# core.net
KiCad netlist of a schematic drawn in Altium Designer
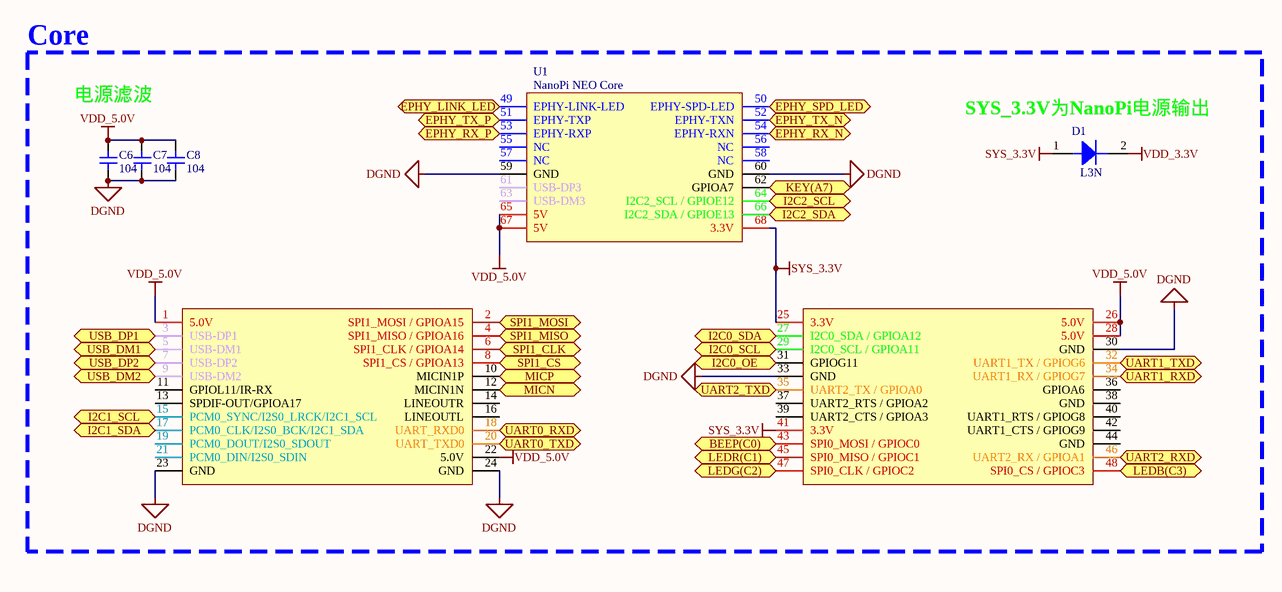
[diagram p0: core.SchDoc]

(export (version "E")
  (design (tool "Eeschema 10.0.6"))
  (components
    (comp (ref "C6")
      (value "104")
      (footprint "0805C")
      (description "无极贴片电容")
      (libsource (lib "集大电协1.5") (part "Cap1"))
    )
    (comp (ref "C7")
      (value "104")
      (footprint "0805C")
      (description "无极贴片电容")
      (libsource (lib "集大电协1.5") (part "Cap1"))
    )
    (comp (ref "C8")
      (value "104")
      (footprint "0805C")
      (description "无极贴片电容")
      (libsource (lib "集大电协1.5") (part "Cap1"))
    )
    (comp (ref "D1")
      (value "L3N")
      (footprint "SOD-123")
      (description "二极管30V/2A")
      (libsource (lib "集大电协1.5") (part "Diode"))
    )
    (comp (ref "U1")
      (value "NanoPi NEO Core")
      (footprint "NanoPi NEO Core(无引脚名)")
      (libsource (lib "集大电协1.5") (part "NanoPi NEO Core"))
    )
  )
  (nets
    (net (code "1") (name "/BEEP(C0)") (class "Default")
      (node (ref "U1") (pin "43") (pinfunction "SPI0_MOSI_/_GPIOC0_43") (pintype "passive"))
    )
    (net (code "2") (name "/EPHY_LINK_LED") (class "Default")
      (node (ref "U1") (pin "49") (pinfunction "EPHY-LINK-LED_49") (pintype "passive"))
    )
    (net (code "3") (name "/EPHY_RX_N") (class "Default")
      (node (ref "U1") (pin "54") (pinfunction "EPHY-RXN_54") (pintype "passive"))
    )
    (net (code "4") (name "/EPHY_RX_P") (class "Default")
      (node (ref "U1") (pin "53") (pinfunction "EPHY-RXP_53") (pintype "passive"))
    )
    (net (code "5") (name "/EPHY_SPD_LED") (class "Default")
      (node (ref "U1") (pin "50") (pinfunction "EPHY-SPD-LED_50") (pintype "passive"))
    )
    (net (code "6") (name "/EPHY_TX_N") (class "Default")
      (node (ref "U1") (pin "52") (pinfunction "EPHY-TXN_52") (pintype "passive"))
    )
    (net (code "7") (name "/EPHY_TX_P") (class "Default")
      (node (ref "U1") (pin "51") (pinfunction "EPHY-TXP_51") (pintype "passive"))
    )
    (net (code "8") (name "/I2C0_OE") (class "Default")
      (node (ref "U1") (pin "31") (pinfunction "GPIOG11_31") (pintype "passive"))
    )
    (net (code "9") (name "/I2C0_SCL") (class "Default")
      (node (ref "U1") (pin "29") (pinfunction "I2C0_SCL_/_GPIOA11_29") (pintype "passive"))
    )
    (net (code "10") (name "/I2C0_SDA") (class "Default")
      (node (ref "U1") (pin "27") (pinfunction "I2C0_SDA_/_GPIOA12_27") (pintype "passive"))
    )
    (net (code "11") (name "/I2C1_SCL") (class "Default")
      (node (ref "U1") (pin "15") (pinfunction "PCM0_SYNC/I2S0_LRCK/I2C1_SCL_15") (pintype "passive"))
    )
    (net (code "12") (name "/I2C1_SDA") (class "Default")
      (node (ref "U1") (pin "17") (pinfunction "PCM0_CLK/I2S0_BCK/I2C1_SDA_17") (pintype "passive"))
    )
    (net (code "13") (name "/I2C2_SCL") (class "Default")
      (node (ref "U1") (pin "64") (pinfunction "I2C2_SCL_/_GPIOE12_64") (pintype "passive"))
    )
    (net (code "14") (name "/I2C2_SDA") (class "Default")
      (node (ref "U1") (pin "66") (pinfunction "I2C2_SDA_/_GPIOE13_66") (pintype "passive"))
    )
    (net (code "15") (name "/KEY(A7)") (class "Default")
      (node (ref "U1") (pin "62") (pinfunction "GPIOA7_62") (pintype "passive"))
    )
    (net (code "16") (name "/LEDB(C3)") (class "Default")
      (node (ref "U1") (pin "48") (pinfunction "SPI0_CS_/_GPIOC3_48") (pintype "passive"))
    )
    (net (code "17") (name "/LEDG(C2)") (class "Default")
      (node (ref "U1") (pin "47") (pinfunction "SPI0_CLK_/_GPIOC2_47") (pintype "passive"))
    )
    (net (code "18") (name "/LEDR(C1)") (class "Default")
      (node (ref "U1") (pin "45") (pinfunction "SPI0_MISO_/_GPIOC1_45") (pintype "passive"))
    )
    (net (code "19") (name "/MICN") (class "Default")
      (node (ref "U1") (pin "12") (pinfunction "MICIN1N_12") (pintype "passive"))
    )
    (net (code "20") (name "/MICP") (class "Default")
      (node (ref "U1") (pin "10") (pinfunction "MICIN1P_10") (pintype "passive"))
    )
    (net (code "21") (name "/SPI1_CLK") (class "Default")
      (node (ref "U1") (pin "6") (pinfunction "SPI1_CLK_/_GPIOA14_6") (pintype "passive"))
    )
    (net (code "22") (name "/SPI1_CS") (class "Default")
      (node (ref "U1") (pin "8") (pinfunction "SPI1_CS_/_GPIOA13_8") (pintype "passive"))
    )
    (net (code "23") (name "/SPI1_MISO") (class "Default")
      (node (ref "U1") (pin "4") (pinfunction "SPI1_MISO_/_GPIOA16_4") (pintype "passive"))
    )
    (net (code "24") (name "/SPI1_MOSI") (class "Default")
      (node (ref "U1") (pin "2") (pinfunction "SPI1_MOSI_/_GPIOA15_2") (pintype "passive"))
    )
    (net (code "25") (name "/UART0_RXD") (class "Default")
      (node (ref "U1") (pin "18") (pinfunction "UART_RXD0_18") (pintype "passive"))
    )
    (net (code "26") (name "/UART0_TXD") (class "Default")
      (node (ref "U1") (pin "20") (pinfunction "UART_TXD0_20") (pintype "passive"))
    )
    (net (code "27") (name "/UART1_RXD") (class "Default")
      (node (ref "U1") (pin "34") (pinfunction "UART1_RX_/_GPIOG7_34") (pintype "passive"))
    )
    (net (code "28") (name "/UART1_TXD") (class "Default")
      (node (ref "U1") (pin "32") (pinfunction "UART1_TX_/_GPIOG6_32") (pintype "passive"))
    )
    (net (code "29") (name "/UART2_RXD") (class "Default")
      (node (ref "U1") (pin "46") (pinfunction "UART2_RX_/_GPIOA1_46") (pintype "passive"))
    )
    (net (code "30") (name "/UART2_TXD") (class "Default")
      (node (ref "U1") (pin "35") (pinfunction "UART2_TX_/_GPIOA0_35") (pintype "passive"))
    )
    (net (code "31") (name "/USB_DM1") (class "Default")
      (node (ref "U1") (pin "5") (pinfunction "USB-DM1_5") (pintype "passive"))
    )
    (net (code "32") (name "/USB_DM2") (class "Default")
      (node (ref "U1") (pin "9") (pinfunction "USB-DM2_9") (pintype "passive"))
    )
    (net (code "33") (name "/USB_DP1") (class "Default")
      (node (ref "U1") (pin "3") (pinfunction "USB-DP1_3") (pintype "passive"))
    )
    (net (code "34") (name "/USB_DP2") (class "Default")
      (node (ref "U1") (pin "7") (pinfunction "USB-DP2_7") (pintype "passive"))
    )
    (net (code "35") (name "DGND") (class "Default")
      (node (ref "C6") (pin "1") (pinfunction "1_1") (pintype "passive"))
      (node (ref "C7") (pin "1") (pinfunction "1_1") (pintype "passive"))
      (node (ref "C8") (pin "1") (pinfunction "1_1") (pintype "passive"))
      (node (ref "U1") (pin "23") (pinfunction "GND_23") (pintype "passive"))
      (node (ref "U1") (pin "24") (pinfunction "GND_24") (pintype "passive"))
      (node (ref "U1") (pin "30") (pinfunction "GND_30") (pintype "passive"))
      (node (ref "U1") (pin "33") (pinfunction "GND_33") (pintype "passive"))
      (node (ref "U1") (pin "59") (pinfunction "GND_59") (pintype "passive"))
      (node (ref "U1") (pin "60") (pinfunction "GND_60") (pintype "passive"))
    )
    (net (code "36") (name "SYS_3.3V") (class "Default")
      (node (ref "D1") (pin "1") (pintype "passive"))
      (node (ref "U1") (pin "25") (pinfunction "3.3V_25") (pintype "passive"))
      (node (ref "U1") (pin "41") (pinfunction "3.3V_41") (pintype "passive"))
      (node (ref "U1") (pin "68") (pinfunction "3.3V_68") (pintype "passive"))
    )
    (net (code "37") (name "VDD_3.3V") (class "Default")
      (node (ref "D1") (pin "2") (pinfunction "2_2") (pintype "passive"))
    )
    (net (code "38") (name "VDD_5.0V") (class "Default")
      (node (ref "C6") (pin "2") (pinfunction "2_2") (pintype "passive"))
      (node (ref "C7") (pin "2") (pinfunction "2_2") (pintype "passive"))
      (node (ref "C8") (pin "2") (pinfunction "2_2") (pintype "passive"))
      (node (ref "U1") (pin "1") (pinfunction "5.0V_1") (pintype "passive"))
      (node (ref "U1") (pin "22") (pinfunction "5.0V_22") (pintype "passive"))
      (node (ref "U1") (pin "26") (pinfunction "5.0V_26") (pintype "passive"))
      (node (ref "U1") (pin "28") (pinfunction "5.0V_28") (pintype "passive"))
      (node (ref "U1") (pin "65") (pinfunction "5V_65") (pintype "passive"))
      (node (ref "U1") (pin "67") (pinfunction "5V_67") (pintype "passive"))
    )
    (net (code "39") (name "unconnected-(U1-GND-Pad38)") (class "Default")
      (node (ref "U1") (pin "38") (pinfunction "GND_38") (pintype "passive"))
    )
    (net (code "40") (name "unconnected-(U1-GND-Pad44)") (class "Default")
      (node (ref "U1") (pin "44") (pinfunction "GND_44") (pintype "passive"))
    )
    (net (code "41") (name "unconnected-(U1-GPIOA6-Pad36)") (class "Default")
      (node (ref "U1") (pin "36") (pinfunction "GPIOA6_36") (pintype "passive"))
    )
    (net (code "42") (name "unconnected-(U1-GPIOL11{slash}IR-RX-Pad11)") (class "Default")
      (node (ref "U1") (pin "11") (pinfunction "GPIOL11/IR-RX_11") (pintype "passive"))
    )
    (net (code "43") (name "unconnected-(U1-LINEOUTL-Pad16)") (class "Default")
      (node (ref "U1") (pin "16") (pinfunction "LINEOUTL_16") (pintype "passive"))
    )
    (net (code "44") (name "unconnected-(U1-LINEOUTR-Pad14)") (class "Default")
      (node (ref "U1") (pin "14") (pinfunction "LINEOUTR_14") (pintype "passive"))
    )
    (net (code "45") (name "unconnected-(U1-NC-Pad55)") (class "Default")
      (node (ref "U1") (pin "55") (pinfunction "NC_55") (pintype "passive"))
    )
    (net (code "46") (name "unconnected-(U1-NC-Pad56)") (class "Default")
      (node (ref "U1") (pin "56") (pinfunction "NC_56") (pintype "passive"))
    )
    (net (code "47") (name "unconnected-(U1-NC-Pad57)") (class "Default")
      (node (ref "U1") (pin "57") (pinfunction "NC_57") (pintype "passive"))
    )
    (net (code "48") (name "unconnected-(U1-NC-Pad58)") (class "Default")
      (node (ref "U1") (pin "58") (pinfunction "NC_58") (pintype "passive"))
    )
    (net (code "49") (name "unconnected-(U1-PCM0_DIN{slash}I2S0_SDIN-Pad21)") (class "Default")
      (node (ref "U1") (pin "21") (pinfunction "PCM0_DIN/I2S0_SDIN_21") (pintype "passive"))
    )
    (net (code "50") (name "unconnected-(U1-PCM0_DOUT{slash}I2S0_SDOUT-Pad19)") (class "Default")
      (node (ref "U1") (pin "19") (pinfunction "PCM0_DOUT/I2S0_SDOUT_19") (pintype "passive"))
    )
    (net (code "51") (name "unconnected-(U1-SPDIF-OUT{slash}GPIOA17-Pad13)") (class "Default")
      (node (ref "U1") (pin "13") (pinfunction "SPDIF-OUT/GPIOA17_13") (pintype "passive"))
    )
    (net (code "52") (name "unconnected-(U1-UART1_CTS_{slash}_GPIOG9-Pad42)") (class "Default")
      (node (ref "U1") (pin "42") (pinfunction "UART1_CTS_/_GPIOG9_42") (pintype "passive"))
    )
    (net (code "53") (name "unconnected-(U1-UART1_RTS_{slash}_GPIOG8-Pad40)") (class "Default")
      (node (ref "U1") (pin "40") (pinfunction "UART1_RTS_/_GPIOG8_40") (pintype "passive"))
    )
    (net (code "54") (name "unconnected-(U1-UART2_CTS_{slash}_GPIOA3-Pad39)") (class "Default")
      (node (ref "U1") (pin "39") (pinfunction "UART2_CTS_/_GPIOA3_39") (pintype "passive"))
    )
    (net (code "55") (name "unconnected-(U1-UART2_RTS_{slash}_GPIOA2-Pad37)") (class "Default")
      (node (ref "U1") (pin "37") (pinfunction "UART2_RTS_/_GPIOA2_37") (pintype "passive"))
    )
    (net (code "56") (name "unconnected-(U1-USB-DM3-Pad63)") (class "Default")
      (node (ref "U1") (pin "63") (pinfunction "USB-DM3_63") (pintype "passive"))
    )
    (net (code "57") (name "unconnected-(U1-USB-DP3-Pad61)") (class "Default")
      (node (ref "U1") (pin "61") (pinfunction "USB-DP3_61") (pintype "passive"))
    )
  )
)
